# miscellaneous.net
KiCad netlist of a schematic drawn in Altium Designer
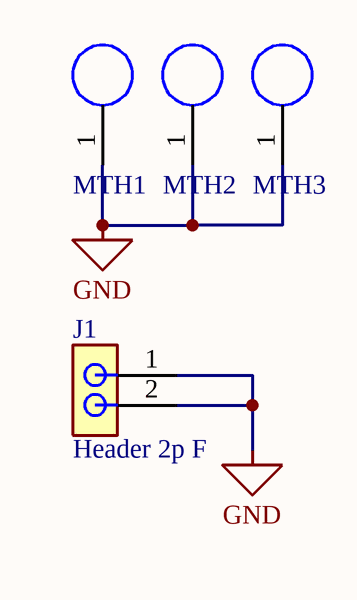
[diagram p0: miscellaneous.SchDoc]

(export (version "E")
  (design (tool "Eeschema 10.0.6"))
  (components
    (comp (ref "J1")
      (value "Header 2p F")
      (footprint "Pin header 2p - F")
      (description "Connector")
      (fields (field (name "MANUFACTURER_PART_NUMBER") "DS1021-1*2SF11-B"))
      (libsource (lib "Kubikova ultra knihovna") (part "Pin header 2p_F"))
    )
    (comp (ref "MTH1")
      (value "Hole")
      (footprint "3.2/6 MM")
      (description "Universal mounting hole plated")
      (libsource (lib "Kubikova ultra knihovna") (part "Hole"))
    )
    (comp (ref "MTH2")
      (value "Hole")
      (footprint "3.2/6 MM")
      (description "Universal mounting hole plated")
      (libsource (lib "Kubikova ultra knihovna") (part "Hole"))
    )
    (comp (ref "MTH3")
      (value "Hole")
      (footprint "3.2/6 MM")
      (description "Universal mounting hole plated")
      (libsource (lib "Kubikova ultra knihovna") (part "Hole"))
    )
  )
  (nets
    (net (code "1") (name "GND") (class "Default")
      (node (ref "J1") (pin "1") (pinfunction "1_1") (pintype "passive"))
      (node (ref "J1") (pin "2") (pinfunction "2_2") (pintype "passive"))
      (node (ref "MTH1") (pin "1") (pintype "passive"))
      (node (ref "MTH2") (pin "1") (pintype "passive"))
      (node (ref "MTH3") (pin "1") (pintype "passive"))
    )
  )
)
